# 7_Humidifier.net
KiCad netlist of a schematic drawn in Altium Designer
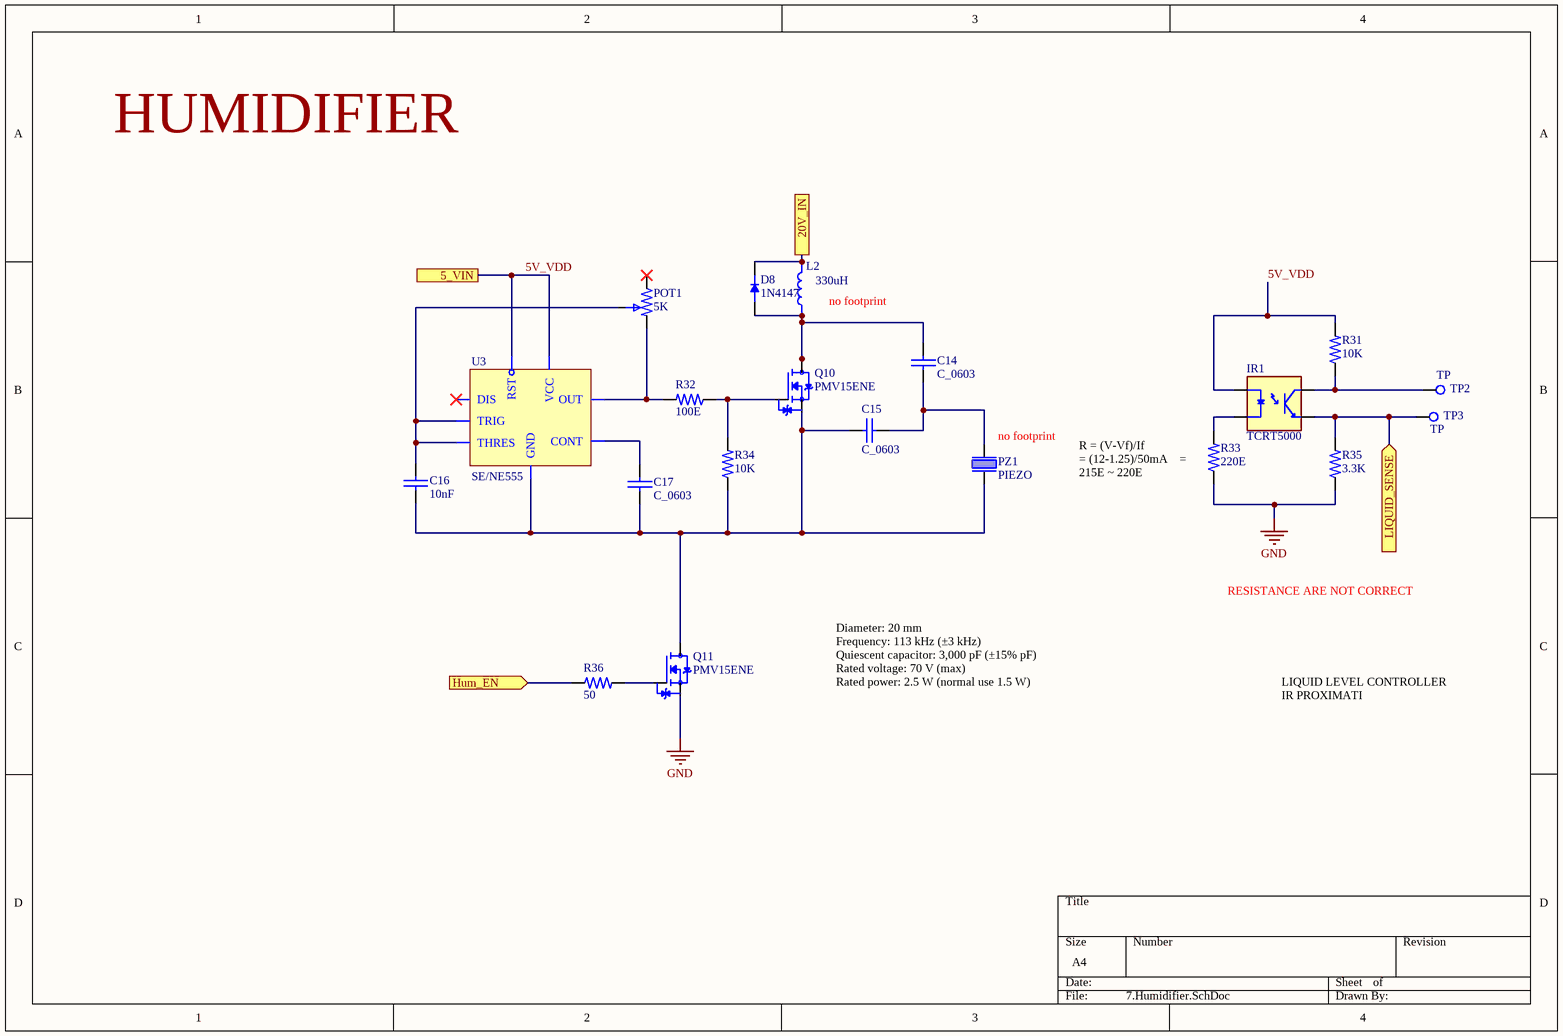
[diagram p0: 7.Humidifier.SchDoc]

(export (version "E")
  (design (tool "Eeschema 10.0.6"))
  (components
    (comp (ref "C14") (value "C_0603") (footprint "PcbLib:C_0603") (libsource (lib "Schlib") (part "C_0603")))
    (comp (ref "C15") (value "C_0603") (footprint "PcbLib:C_0603") (libsource (lib "Schlib") (part "C_0603")))
    (comp (ref "C16") (value "10nF") (footprint "PcbLib:C_0603") (libsource (lib "Schlib") (part "C_0603")))
    (comp (ref "C17") (value "C_0603") (footprint "PcbLib:C_0603") (libsource (lib "Schlib") (part "C_0603")))
    (comp (ref "D8")
      (value "1N4147")
      (footprint "SOD123")
      (fields (field (name "MFR") "Panjit"))
      (libsource (lib "Schlib") (part "1N4147"))
    )
    (comp (ref "IR1")
      (value "TCRT5000")
      (footprint "TCRT5000")
      (fields (field (name "MFR") "Vishay Semiconductors"))
      (libsource (lib "Schlib") (part "TCRT5000"))
    )
    (comp (ref "L2") (value "330uH") (footprint "2P5mm_PITCH_COM") (libsource (lib "Schlib") (part "L_COM")))
    (comp (ref "POT1")
      (value "5K")
      (footprint "TC33 - 3 mm SMD Trimpot")
      (fields (field (name "MFR") "Bourns"))
      (libsource (lib "Schlib") (part "TC33 - 3 mm SMD Trimpot"))
    )
    (comp (ref "PZ1") (value "PIEZO") (footprint "2P5mm_PITCH_COM") (libsource (lib "Schlib") (part "PIEZO")))
    (comp (ref "Q10")
      (value "PMV15ENE")
      (footprint "SOT23FR")
      (fields (field (name "MFR") "Nexperia"))
      (libsource (lib "Schlib") (part "PMV15ENE"))
    )
    (comp (ref "Q11")
      (value "PMV15ENE")
      (footprint "SOT23FR")
      (fields (field (name "MFR") "Nexperia"))
      (libsource (lib "Schlib") (part "PMV15ENE"))
    )
    (comp (ref "R31") (value "10K") (footprint "R_0603") (libsource (lib "Schlib") (part "R_0603")))
    (comp (ref "R32") (value "100E") (footprint "R_0603") (libsource (lib "Schlib") (part "R_0603")))
    (comp (ref "R33") (value "220E") (footprint "R_0603") (libsource (lib "Schlib") (part "R_0603")))
    (comp (ref "R34") (value "10K") (footprint "R_0603") (libsource (lib "Schlib") (part "R_0603")))
    (comp (ref "R35") (value "3.3K") (footprint "R_0603") (libsource (lib "Schlib") (part "R_0603")))
    (comp (ref "R36") (value "50") (footprint "R_0603") (libsource (lib "Schlib") (part "R_0603")))
    (comp (ref "TP2") (value "TP") (libsource (lib "Schlib") (part "TP")))
    (comp (ref "TP3") (value "TP") (libsource (lib "Schlib") (part "TP")))
    (comp (ref "U3")
      (value "SE/NE555")
      (footprint "SOIC-8")
      (fields (field (name "MFR") "Diodes Incorporated"))
      (libsource (lib "Schlib") (part "SE/NE555"))
    )
  )
  (nets
    (net (code "1") (name "/5V_VDD") (class "Default")
      (node (ref "IR1") (pin "A") (pinfunction "A_A") (pintype "passive"))
      (node (ref "R31") (pin "2") (pinfunction "2_2") (pintype "passive"))
      (node (ref "U3") (pin "4") (pinfunction "RST_4") (pintype "passive"))
      (node (ref "U3") (pin "8") (pinfunction "VCC_8") (pintype "power_in"))
    )
    (net (code "2") (name "/20V_IN") (class "Default")
      (node (ref "D8") (pin "C") (pinfunction "K_C") (pintype "passive"))
      (node (ref "L2") (pin "2") (pinfunction "2_2") (pintype "passive"))
    )
    (net (code "3") (name "/Hum_EN") (class "Default")
      (node (ref "R36") (pin "1") (pinfunction "1_1") (pintype "passive"))
    )
    (net (code "4") (name "/LIQUID_SENSE") (class "Default")
      (node (ref "IR1") (pin "E") (pinfunction "E_E") (pintype "passive"))
      (node (ref "R35") (pin "2") (pinfunction "2_2") (pintype "passive"))
      (node (ref "TP3") (pin "1") (pinfunction "1_1") (pintype "passive"))
    )
    (net (code "5") (name "GND") (class "Default")
      (node (ref "Q11") (pin "3") (pinfunction "S_3") (pintype "passive"))
      (node (ref "R33") (pin "1") (pinfunction "1_1") (pintype "passive"))
      (node (ref "R35") (pin "1") (pinfunction "1_1") (pintype "passive"))
    )
    (net (code "6") (name "Net-(C14-Pad1)") (class "Default")
      (node (ref "C14") (pin "1") (pinfunction "1_1") (pintype "passive"))
      (node (ref "C15") (pin "1") (pinfunction "1_1") (pintype "passive"))
      (node (ref "PZ1") (pin "2") (pinfunction "2_2") (pintype "passive"))
    )
    (net (code "7") (name "Net-(IR1-PadCATH)") (class "Default")
      (node (ref "IR1") (pin "CATH") (pinfunction "CATH_CATH") (pintype "passive"))
      (node (ref "R33") (pin "2") (pinfunction "2_2") (pintype "passive"))
    )
    (net (code "8") (name "Net-(IR1-PadCOLL)") (class "Default")
      (node (ref "IR1") (pin "COLL") (pinfunction "COLL_COLL") (pintype "passive"))
      (node (ref "R31") (pin "1") (pinfunction "1_1") (pintype "passive"))
      (node (ref "TP2") (pin "1") (pinfunction "1_1") (pintype "passive"))
    )
    (net (code "9") (name "Net-(POT1-CW)") (class "Default")
      (node (ref "POT1") (pin "3") (pinfunction "CW_3") (pintype "passive"))
      (node (ref "R32") (pin "2") (pinfunction "2_2") (pintype "passive"))
      (node (ref "U3") (pin "3") (pinfunction "OUT_3") (pintype "passive"))
    )
    (net (code "10") (name "Net-(POT1-W)") (class "Default")
      (node (ref "C16") (pin "2") (pinfunction "2_2") (pintype "passive"))
      (node (ref "POT1") (pin "2") (pinfunction "W_2") (pintype "passive"))
      (node (ref "U3") (pin "2") (pinfunction "TRIG_2") (pintype "passive"))
      (node (ref "U3") (pin "6") (pinfunction "THRES_6") (pintype "passive"))
    )
    (net (code "11") (name "Net-(Q10-D)") (class "Default")
      (node (ref "C14") (pin "2") (pinfunction "2_2") (pintype "passive"))
      (node (ref "D8") (pin "A") (pinfunction "A_A") (pintype "passive"))
      (node (ref "L2") (pin "1") (pinfunction "1_1") (pintype "passive"))
      (node (ref "Q10") (pin "1") (pinfunction "D_1") (pintype "passive"))
    )
    (net (code "12") (name "Net-(Q10-G)") (class "Default")
      (node (ref "Q10") (pin "2") (pinfunction "G_2") (pintype "passive"))
      (node (ref "R32") (pin "1") (pinfunction "1_1") (pintype "passive"))
      (node (ref "R34") (pin "2") (pinfunction "2_2") (pintype "passive"))
    )
    (net (code "13") (name "Net-(Q10-S)") (class "Default")
      (node (ref "C15") (pin "2") (pinfunction "2_2") (pintype "passive"))
      (node (ref "C16") (pin "1") (pinfunction "1_1") (pintype "passive"))
      (node (ref "C17") (pin "1") (pinfunction "1_1") (pintype "passive"))
      (node (ref "PZ1") (pin "1") (pinfunction "1_1") (pintype "passive"))
      (node (ref "Q10") (pin "3") (pinfunction "S_3") (pintype "passive"))
      (node (ref "Q11") (pin "1") (pinfunction "D_1") (pintype "passive"))
      (node (ref "R34") (pin "1") (pinfunction "1_1") (pintype "passive"))
      (node (ref "U3") (pin "1") (pinfunction "GND_1") (pintype "power_in"))
    )
    (net (code "14") (name "Net-(Q11-G)") (class "Default")
      (node (ref "Q11") (pin "2") (pinfunction "G_2") (pintype "passive"))
      (node (ref "R36") (pin "2") (pinfunction "2_2") (pintype "passive"))
    )
    (net (code "15") (name "Net-(U3-CONT)") (class "Default")
      (node (ref "C17") (pin "2") (pinfunction "2_2") (pintype "passive"))
      (node (ref "U3") (pin "5") (pinfunction "CONT_5") (pintype "passive"))
    )
    (net (code "16") (name "unconnected-(POT1-CCW-Pad1)") (class "Default")
      (node (ref "POT1") (pin "1") (pinfunction "CCW_1") (pintype "passive+no_connect"))
    )
    (net (code "17") (name "unconnected-(U3-DIS-Pad7)") (class "Default")
      (node (ref "U3") (pin "7") (pinfunction "DIS_7") (pintype "passive+no_connect"))
    )
  )
)
